# arduino_schDoc.net
KiCad netlist of a schematic drawn in Altium Designer
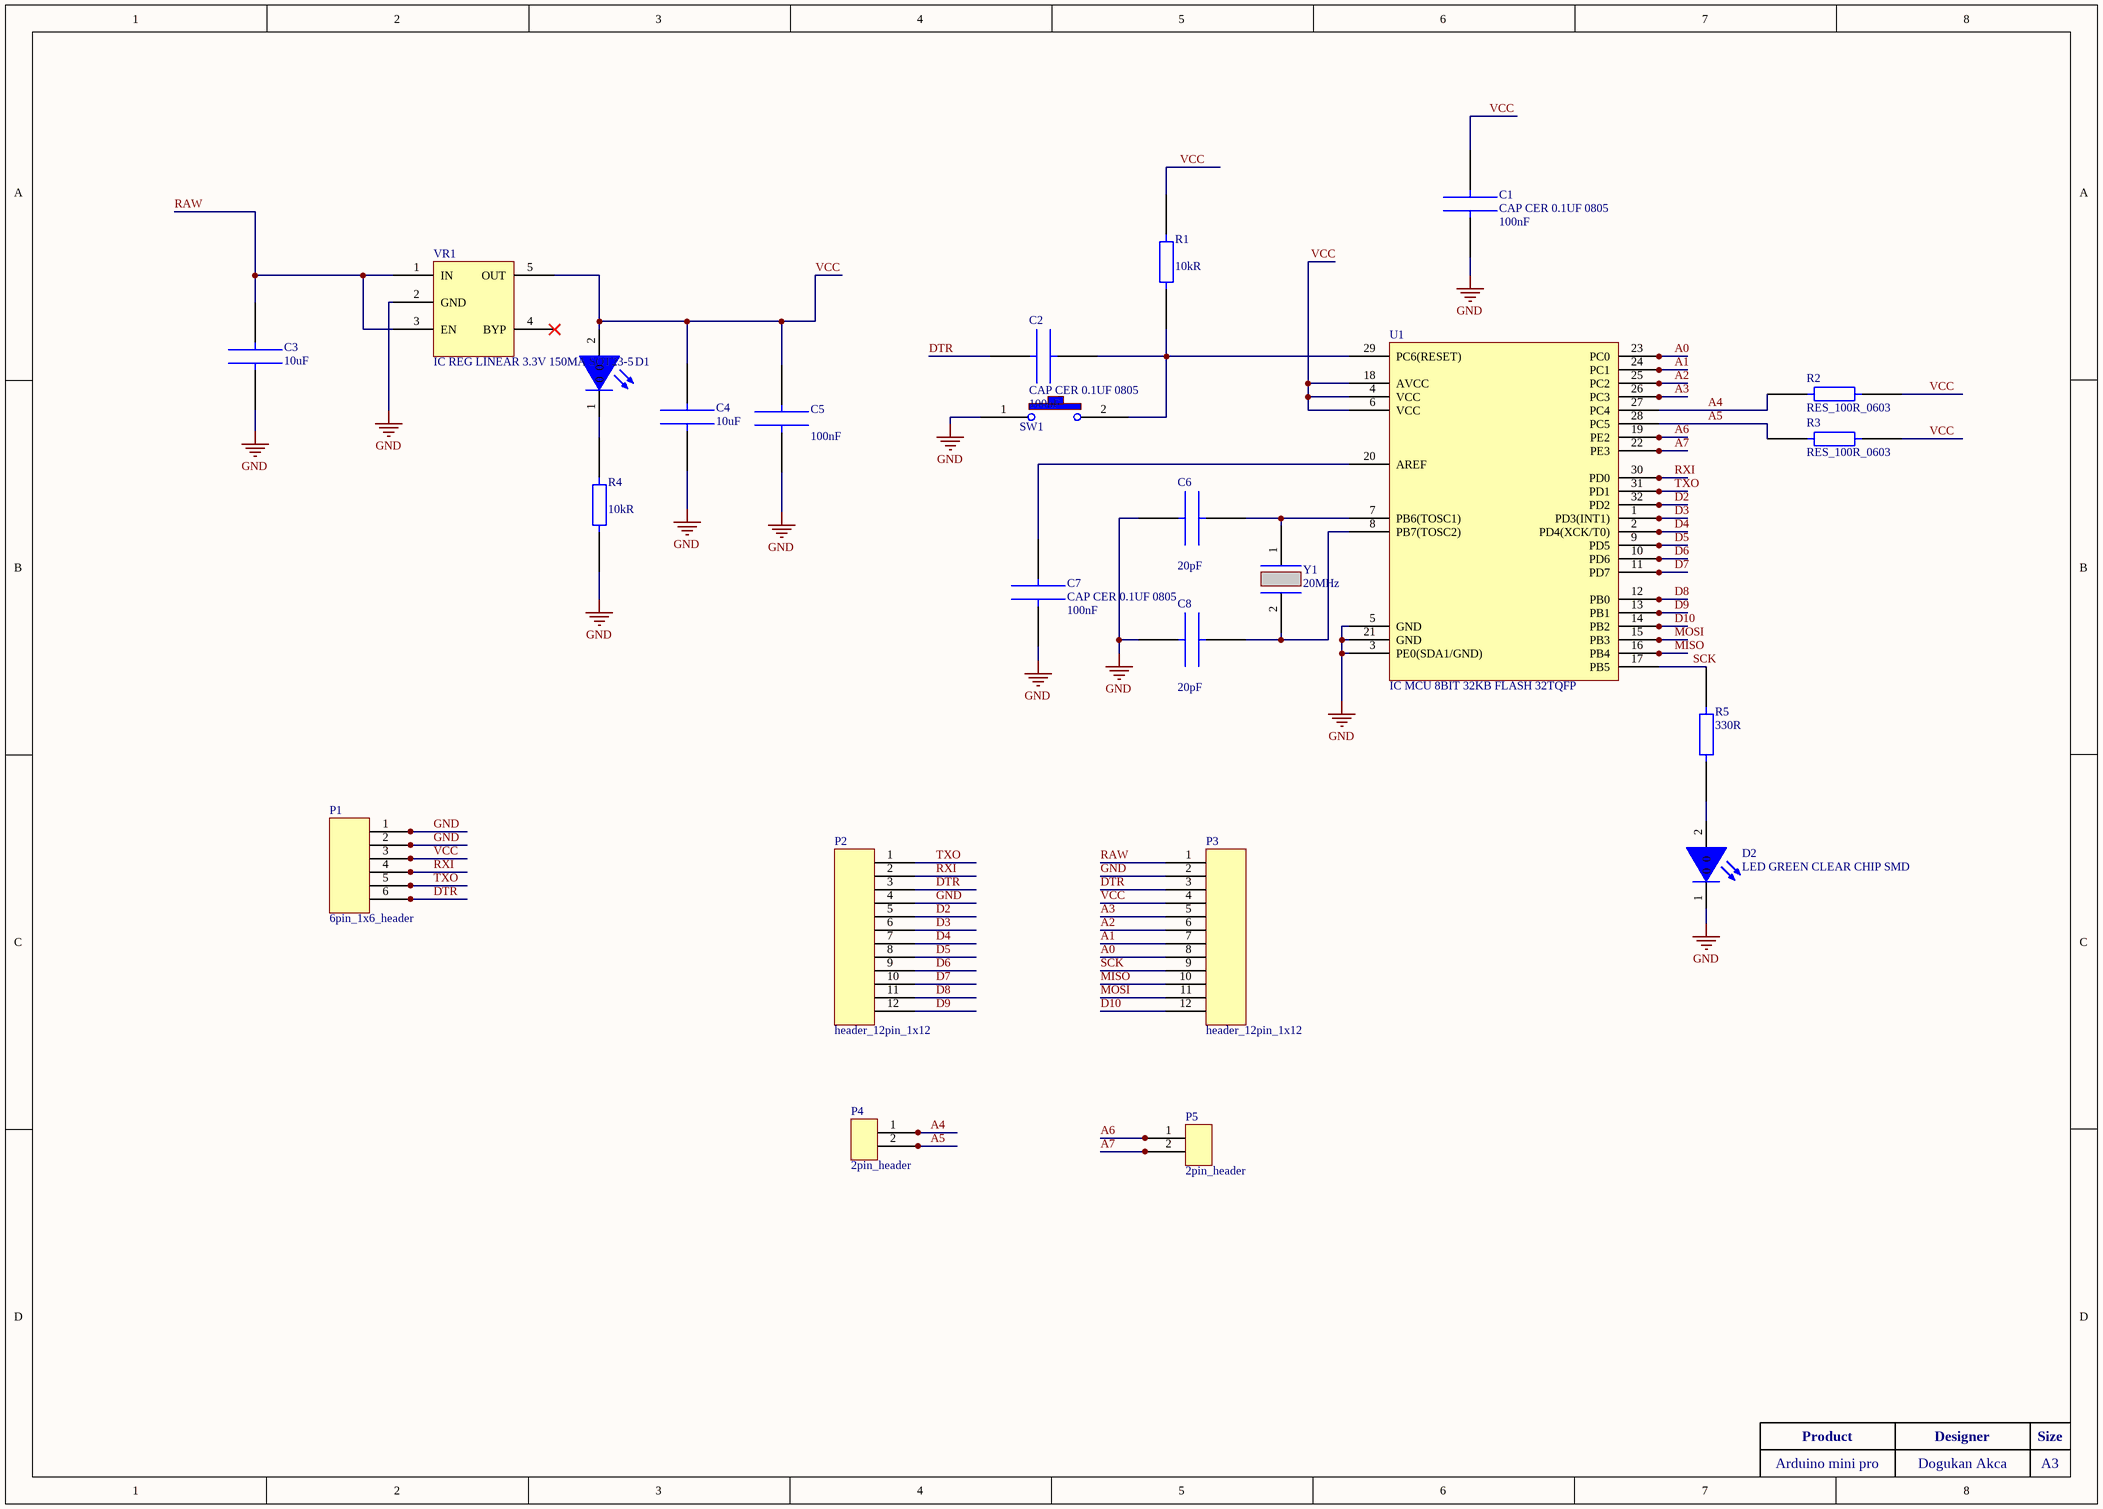
[diagram p0: arduino_schDoc.SchDoc]

(export (version "E")
  (design (tool "Eeschema 10.0.6"))
  (components
    (comp (ref "C1")
      (value "CAP CER 0.1UF 0805")
      (footprint "CAP_0805")
      (description "CAP CER 0.1UF 50V X7R 0805")
      (fields
        (field (name "MANUFACTURER") "Samsung")
        (field (name "MANUFACTURER PART NUMBER") "CL21B104KBCNNNC")
        (field (name "CAPACITANCE") "100nF")
        (field (name "DESIGNER") "Dogukan")
      )
      (libsource (lib "arduino_integratedLib") (part "CAP CER 0.1UF 0805"))
    )
    (comp (ref "C2")
      (value "CAP CER 0.1UF 0805")
      (footprint "CAP_0805")
      (description "CAP CER 0.1UF 50V X7R 0805")
      (fields
        (field (name "MANUFACTURER") "Samsung")
        (field (name "MANUFACTURER PART NUMBER") "CL21B104KBCNNNC")
        (field (name "CAPACITANCE") "100nF")
        (field (name "DESIGNER") "Dogukan")
      )
      (libsource (lib "arduino_integratedLib") (part "CAP CER 0.1UF 0805"))
    )
    (comp (ref "C3")
      (value "*CAP CER 10UF 4V X5R 0603")
      (footprint "0603_CAP")
      (description "0603 10 uF 4 V ±20% Tolerance X5R Multilayer Ceramic Capacitor")
      (fields
        (field (name "MANUFACTURER") "Yageo")
        (field (name "MANUFACTURER PART NUMBER") "CC0603MRX5R4BB106")
        (field (name "FARAD") "10uF")
        (field (name "DESIGNER") "Dogukan")
      )
      (libsource (lib "arduino_integratedLib") (part "CAP CER 10UF 4V X5R 0603"))
    )
    (comp (ref "C4")
      (value "*CAP CER 10UF 4V X5R 0603")
      (footprint "0603_CAP")
      (description "0603 10 uF 4 V ±20% Tolerance X5R Multilayer Ceramic Capacitor")
      (fields
        (field (name "MANUFACTURER") "Yageo")
        (field (name "MANUFACTURER PART NUMBER") "CC0603MRX5R4BB106")
        (field (name "FARAD") "10uF")
        (field (name "DESIGNER") "Dogukan")
      )
      (libsource (lib "arduino_integratedLib") (part "CAP CER 10UF 4V X5R 0603"))
    )
    (comp (ref "C5")
      (value "CAP CER 0.1UF 0805")
      (footprint "CAP_0805")
      (description "CAP CER 0.1UF 50V X7R 0805")
      (fields
        (field (name "MANUFACTURER") "Samsung")
        (field (name "MANUFACTURER PART NUMBER") "CL21B104KBCNNNC")
        (field (name "CAPACITANCE") "100nF")
        (field (name "DESIGNER") "Dogukan")
      )
      (libsource (lib "arduino_integratedLib") (part "CAP CER 0.1UF 0805"))
    )
    (comp (ref "C6")
      (value "CAP CER 20PF 50V C0G/NP0 0603")
      (footprint "0603_CAP")
      (fields
        (field (name "MANUFACTURER") "Samsung")
        (field (name "MANUFACTURER PART NUMBER") "CL10C200JB8NNNC")
        (field (name "TOLERANCE") "5%")
        (field (name "CAPACITANCE") "20pF")
        (field (name "DESIGNER") "Dogukan")
      )
      (libsource (lib "arduino_integratedLib") (part "CAP CER 20PF 50V C0G/NP0 0603"))
    )
    (comp (ref "C7")
      (value "CAP CER 0.1UF 0805")
      (footprint "CAP_0805")
      (description "CAP CER 0.1UF 50V X7R 0805")
      (fields
        (field (name "MANUFACTURER") "Samsung")
        (field (name "MANUFACTURER PART NUMBER") "CL21B104KBCNNNC")
        (field (name "CAPACITANCE") "100nF")
        (field (name "DESIGNER") "Dogukan")
      )
      (libsource (lib "arduino_integratedLib") (part "CAP CER 0.1UF 0805"))
    )
    (comp (ref "C8")
      (value "CAP CER 20PF 50V C0G/NP0 0603")
      (footprint "0603_CAP")
      (fields
        (field (name "MANUFACTURER") "Samsung")
        (field (name "MANUFACTURER PART NUMBER") "CL10C200JB8NNNC")
        (field (name "TOLERANCE") "5%")
        (field (name "CAPACITANCE") "20pF")
        (field (name "DESIGNER") "Dogukan")
      )
      (libsource (lib "arduino_integratedLib") (part "CAP CER 20PF 50V C0G/NP0 0603"))
    )
    (comp (ref "D1")
      (value "LED RED DIFFUSED 0805 SMD")
      (footprint "0805_RED_LED")
      (description "Red 645nm LED Indication - Discrete 1.8V 0805 (2012 Metric)")
      (fields (field (name "DESIGNER") "Dogukan"))
      (libsource (lib "arduino_integratedLib") (part "LED RED DIFFUSED 0805 SMD"))
    )
    (comp (ref "D2")
      (value "LED GREEN CLEAR CHIP SMD")
      (footprint "0805_LED_GREEN")
      (description "Green 569nm LED Indication - Discrete 2.1V 0805 (2012 Metric)")
      (fields
        (field (name "MANUFACTURER") "Vishay Lite-On")
        (field (name "MANUFACTURER PART NUMBER") "LTST-C171GKT")
        (field (name "DESIGNER") "Dogukan")
      )
      (libsource (lib "arduino_integratedLib") (part "LED GREEN CLEAR CHIP SMD"))
    )
    (comp (ref "P1")
      (value "6pin_1x6_header")
      (footprint "6_pin_header_1x6")
      (fields (field (name "DESIGNER") "Dogukan"))
      (libsource (lib "arduino_integratedLib") (part "6pin_1x6_header"))
    )
    (comp (ref "P2")
      (value "header_12pin_1x12")
      (footprint "12_pin_header_1x12")
      (fields (field (name "DESIGNER") "Dogukan"))
      (libsource (lib "arduino_integratedLib") (part "header_12pin_1x12"))
    )
    (comp (ref "P3")
      (value "header_12pin_1x12")
      (footprint "12_pin_header_1x12")
      (fields (field (name "DESIGNER") "Dogukan"))
      (libsource (lib "") (part "header_12pin_1x12_1"))
    )
    (comp (ref "P4")
      (value "2pin_header")
      (footprint "2pin_header_1x2")
      (fields (field (name "DESIGNER") "Dogukan"))
      (libsource (lib "") (part "2pin_header_1"))
    )
    (comp (ref "P5")
      (value "2pin_header")
      (footprint "2pin_header_1x2")
      (fields (field (name "DESIGNER") "Dogukan"))
      (libsource (lib "arduino_integratedLib") (part "2pin_header"))
    )
    (comp (ref "R1")
      (value "RES 10K OHM 0.5% 1/10W 0603")
      (footprint "0603_RES")
      (description "Res Thin Film 0603 10K Ohm 0.5% 1/10W ±25ppm/°C Molded SMD Paper T/R")
      (fields
        (field (name "MANUFACTURER") "Yageo")
        (field (name "MANUFACTURER PART NUMBER") "RT0603DRD0710KL")
        (field (name "RESISTANCE") "10kR")
        (field (name "DESIGNER") "Dogukan")
      )
      (libsource (lib "arduino_integratedLib") (part "RES 10K OHM 0.5% 1/10W 0603"))
    )
    (comp (ref "R2")
      (value "RES_100R_0603")
      (footprint "0603_RES")
      (description "Res Thick Film 0603 100 Ohm 1% 1/10W ±100ppm/°C Molded SMD Paper T/R")
      (fields
        (field (name "MANUFACTURER") "Yageo")
        (field (name "MANUFACTURER PART NUMBER") "RC0603FR-07100RL")
        (field (name "DESIGNER") "Dogukan")
      )
      (libsource (lib "arduino_integratedLib") (part "RES_100R_0603"))
    )
    (comp (ref "R3")
      (value "RES_100R_0603")
      (footprint "0603_RES")
      (description "Res Thick Film 0603 100 Ohm 1% 1/10W ±100ppm/°C Molded SMD Paper T/R")
      (fields
        (field (name "MANUFACTURER") "Yageo")
        (field (name "MANUFACTURER PART NUMBER") "RC0603FR-07100RL")
        (field (name "DESIGNER") "Dogukan")
      )
      (libsource (lib "arduino_integratedLib") (part "RES_100R_0603"))
    )
    (comp (ref "R4")
      (value "RES 10K OHM 0.5% 1/10W 0603")
      (footprint "0603_RES")
      (description "Res Thin Film 0603 10K Ohm 0.5% 1/10W ±25ppm/°C Molded SMD Paper T/R")
      (fields
        (field (name "MANUFACTURER") "Yageo")
        (field (name "MANUFACTURER PART NUMBER") "RT0603DRD0710KL")
        (field (name "RESISTANCE") "10kR")
        (field (name "DESIGNER") "Dogukan")
      )
      (libsource (lib "arduino_integratedLib") (part "RES 10K OHM 0.5% 1/10W 0603"))
    )
    (comp (ref "R5")
      (value "330R")
      (footprint "0603_RES")
      (description "Res Thick Film 0201 330 Ohm 1% 1/20W ±200ppm/°C Molded SMD SMD Paper T/R")
      (fields
        (field (name "MANUFACTURER") "Yageo")
        (field (name "MANUFACTURER PART NUMBER") "RC0201FR-07330RL")
        (field (name "DESIGNER") "Dogukan")
      )
      (libsource (lib "arduino_integratedLib") (part "RES 330 OHM 1% 1/20W 0201"))
    )
    (comp (ref "SW1")
      (value "push button switch")
      (footprint "push_button")
      (libsource (lib "arduino_integratedLib") (part "push_button"))
    )
    (comp (ref "U1")
      (value "IC MCU 8BIT 32KB FLASH 32TQFP")
      (footprint "32-TQFP")
      (description "AVR 32KBYTES Flash, 1KBYTES EEPROM, 2KBYTES Ram, W - 20MHZ, TQFP, Extended Temp, Green 5 V T&r")
      (fields
        (field (name "MANUFACTURER") "Microchip")
        (field (name "MANUFACTURER PART NUMBER") "ATMEGA328PB-ANR")
        (field (name "DESIGNER") "Dogukan")
      )
      (libsource (lib "arduino_integratedLib") (part "Atmega MCU 8BIT 32KB FLASH 32TQFP"))
    )
    (comp (ref "VR1")
      (value "IC REG LINEAR 3.3V 150MA SOT23-5")
      (footprint "SOT23-5")
      (description "Linear Voltage Regulator IC Positive Fixed 1 Output 3.3V 150mA SOT-23-5")
      (fields
        (field (name "MANUFACTURER") "Microchip")
        (field (name "MANUFACTURER PART NUMBER") "MIC5205-3.3YM5-TR")
        (field (name "DESIGNER") "Dogukan")
      )
      (libsource (lib "arduino_integratedLib") (part "IC REG LINEAR 3.3V 150MA SOT23-5"))
    )
    (comp (ref "Y1")
      (value "CRYSTAL 20.0000MHZ 20PF SMD")
      (footprint "2-SMD_CRYSTAL 32.7680KHZ")
      (description "Crystal 20MHz ±30ppm (Tol) ±50ppm (Stability) 20pF FUND 30Ohm 2-Pin Mini-SMD T/R")
      (fields
        (field (name "MANUFACTURER") "ECS International")
        (field (name "MANUFACTURER PART NUMBER") "ECS-200-20-23A-EN-TR")
        (field (name "FREQUENCY") "20MHz")
        (field (name "DESIGNER") "Dogukan")
      )
      (libsource (lib "arduino_integratedLib") (part "CRYSTAL 20MHZ SMD"))
    )
  )
  (nets
    (net (code "1") (name "/A0") (class "Default")
      (node (ref "P3") (pin "8") (pinfunction "8_8") (pintype "passive"))
      (node (ref "U1") (pin "23") (pinfunction "PC0_23") (pintype "passive"))
    )
    (net (code "2") (name "/A1") (class "Default")
      (node (ref "P3") (pin "7") (pinfunction "7_7") (pintype "passive"))
      (node (ref "U1") (pin "24") (pinfunction "PC1_24") (pintype "passive"))
    )
    (net (code "3") (name "/A2") (class "Default")
      (node (ref "P3") (pin "6") (pinfunction "6_6") (pintype "passive"))
      (node (ref "U1") (pin "25") (pinfunction "PC2_25") (pintype "passive"))
    )
    (net (code "4") (name "/A3") (class "Default")
      (node (ref "P3") (pin "5") (pinfunction "5_5") (pintype "passive"))
      (node (ref "U1") (pin "26") (pinfunction "PC3_26") (pintype "passive"))
    )
    (net (code "5") (name "/A4") (class "Default")
      (node (ref "P4") (pin "1") (pinfunction "1_1") (pintype "passive"))
      (node (ref "R2") (pin "1") (pinfunction "25_1") (pintype "passive"))
      (node (ref "U1") (pin "27") (pinfunction "PC4_27") (pintype "passive"))
    )
    (net (code "6") (name "/A5") (class "Default")
      (node (ref "P4") (pin "2") (pinfunction "2_2") (pintype "passive"))
      (node (ref "R3") (pin "1") (pinfunction "25_1") (pintype "passive"))
      (node (ref "U1") (pin "28") (pinfunction "PC5_28") (pintype "passive"))
    )
    (net (code "7") (name "/A6") (class "Default")
      (node (ref "P5") (pin "1") (pinfunction "1_1") (pintype "passive"))
      (node (ref "U1") (pin "19") (pinfunction "PE2_19") (pintype "passive"))
    )
    (net (code "8") (name "/A7") (class "Default")
      (node (ref "P5") (pin "2") (pinfunction "2_2") (pintype "passive"))
      (node (ref "U1") (pin "22") (pinfunction "PE3_22") (pintype "passive"))
    )
    (net (code "9") (name "/D2") (class "Default")
      (node (ref "P2") (pin "5") (pinfunction "5_5") (pintype "passive"))
      (node (ref "U1") (pin "32") (pinfunction "PD2_32") (pintype "passive"))
    )
    (net (code "10") (name "/D3") (class "Default")
      (node (ref "P2") (pin "6") (pinfunction "6_6") (pintype "passive"))
      (node (ref "U1") (pin "1") (pinfunction "PD3(INT1)_1") (pintype "passive"))
    )
    (net (code "11") (name "/D4") (class "Default")
      (node (ref "P2") (pin "7") (pinfunction "7_7") (pintype "passive"))
      (node (ref "U1") (pin "2") (pinfunction "PD4(XCK/T0)_2") (pintype "passive"))
    )
    (net (code "12") (name "/D5") (class "Default")
      (node (ref "P2") (pin "8") (pinfunction "8_8") (pintype "passive"))
      (node (ref "U1") (pin "9") (pinfunction "PD5_9") (pintype "passive"))
    )
    (net (code "13") (name "/D6") (class "Default")
      (node (ref "P2") (pin "9") (pinfunction "9_9") (pintype "passive"))
      (node (ref "U1") (pin "10") (pinfunction "PD6_10") (pintype "passive"))
    )
    (net (code "14") (name "/D7") (class "Default")
      (node (ref "P2") (pin "10") (pinfunction "10_10") (pintype "passive"))
      (node (ref "U1") (pin "11") (pinfunction "PD7_11") (pintype "passive"))
    )
    (net (code "15") (name "/D8") (class "Default")
      (node (ref "P2") (pin "11") (pinfunction "11_11") (pintype "passive"))
      (node (ref "U1") (pin "12") (pinfunction "PB0_12") (pintype "passive"))
    )
    (net (code "16") (name "/D9") (class "Default")
      (node (ref "P2") (pin "12") (pinfunction "12_12") (pintype "passive"))
      (node (ref "U1") (pin "13") (pinfunction "PB1_13") (pintype "passive"))
    )
    (net (code "17") (name "/D10") (class "Default")
      (node (ref "P3") (pin "12") (pinfunction "12_12") (pintype "passive"))
      (node (ref "U1") (pin "14") (pinfunction "PB2_14") (pintype "passive"))
    )
    (net (code "18") (name "/DTR") (class "Default")
      (node (ref "C2") (pin "1") (pinfunction "26_1") (pintype "passive"))
      (node (ref "P1") (pin "6") (pinfunction "6_6") (pintype "passive"))
      (node (ref "P2") (pin "3") (pinfunction "3_3") (pintype "passive"))
      (node (ref "P3") (pin "3") (pinfunction "3_3") (pintype "passive"))
    )
    (net (code "19") (name "/MISO") (class "Default")
      (node (ref "P3") (pin "10") (pinfunction "10_10") (pintype "passive"))
      (node (ref "U1") (pin "16") (pinfunction "PB4_16") (pintype "passive"))
    )
    (net (code "20") (name "/MOSI") (class "Default")
      (node (ref "P3") (pin "11") (pinfunction "11_11") (pintype "passive"))
      (node (ref "U1") (pin "15") (pinfunction "PB3_15") (pintype "passive"))
    )
    (net (code "21") (name "/RAW") (class "Default")
      (node (ref "C3") (pin "2") (pinfunction "27_2") (pintype "passive"))
      (node (ref "P3") (pin "1") (pinfunction "1_1") (pintype "passive"))
      (node (ref "VR1") (pin "1") (pinfunction "IN_1") (pintype "passive"))
      (node (ref "VR1") (pin "3") (pinfunction "EN_3") (pintype "passive"))
    )
    (net (code "22") (name "/RXI") (class "Default")
      (node (ref "P1") (pin "4") (pinfunction "4_4") (pintype "passive"))
      (node (ref "P2") (pin "2") (pinfunction "2_2") (pintype "passive"))
      (node (ref "U1") (pin "30") (pinfunction "PD0_30") (pintype "passive"))
    )
    (net (code "23") (name "/SCK") (class "Default")
      (node (ref "P3") (pin "9") (pinfunction "9_9") (pintype "passive"))
      (node (ref "R5") (pin "2") (pinfunction "24_2") (pintype "passive"))
      (node (ref "U1") (pin "17") (pinfunction "PB5_17") (pintype "passive"))
    )
    (net (code "24") (name "/TXO") (class "Default")
      (node (ref "P1") (pin "5") (pinfunction "5_5") (pintype "passive"))
      (node (ref "P2") (pin "1") (pinfunction "1_1") (pintype "passive"))
      (node (ref "U1") (pin "31") (pinfunction "PD1_31") (pintype "passive"))
    )
    (net (code "25") (name "/VCC") (class "Default")
      (node (ref "C1") (pin "2") (pinfunction "27_2") (pintype "passive"))
      (node (ref "C4") (pin "2") (pinfunction "27_2") (pintype "passive"))
      (node (ref "C5") (pin "2") (pinfunction "27_2") (pintype "passive"))
      (node (ref "D1") (pin "2") (pinfunction "0_2") (pintype "passive"))
      (node (ref "P1") (pin "3") (pinfunction "3_3") (pintype "passive"))
      (node (ref "P3") (pin "4") (pinfunction "4_4") (pintype "passive"))
      (node (ref "R1") (pin "2") (pinfunction "24_2") (pintype "passive"))
      (node (ref "R2") (pin "2") (pinfunction "24_2") (pintype "passive"))
      (node (ref "R3") (pin "2") (pinfunction "24_2") (pintype "passive"))
      (node (ref "U1") (pin "18") (pinfunction "AVCC_18") (pintype "passive"))
      (node (ref "U1") (pin "4") (pinfunction "VCC_4") (pintype "passive"))
      (node (ref "U1") (pin "6") (pinfunction "VCC_6") (pintype "passive"))
      (node (ref "VR1") (pin "5") (pinfunction "OUT_5") (pintype "passive"))
    )
    (net (code "26") (name "GND") (class "Default")
      (node (ref "C1") (pin "1") (pinfunction "26_1") (pintype "passive"))
      (node (ref "C3") (pin "1") (pinfunction "26_1") (pintype "passive"))
      (node (ref "C4") (pin "1") (pinfunction "26_1") (pintype "passive"))
      (node (ref "C5") (pin "1") (pinfunction "26_1") (pintype "passive"))
      (node (ref "C6") (pin "1") (pinfunction "26_1") (pintype "passive"))
      (node (ref "C7") (pin "1") (pinfunction "26_1") (pintype "passive"))
      (node (ref "C8") (pin "1") (pinfunction "26_1") (pintype "passive"))
      (node (ref "D2") (pin "1") (pinfunction "0_1") (pintype "passive"))
      (node (ref "P1") (pin "1") (pinfunction "1_1") (pintype "passive"))
      (node (ref "P1") (pin "2") (pinfunction "2_2") (pintype "passive"))
      (node (ref "P2") (pin "4") (pinfunction "4_4") (pintype "passive"))
      (node (ref "P3") (pin "2") (pinfunction "2_2") (pintype "passive"))
      (node (ref "R4") (pin "1") (pinfunction "25_1") (pintype "passive"))
      (node (ref "SW1") (pin "1") (pinfunction "1_1") (pintype "passive"))
      (node (ref "U1") (pin "21") (pinfunction "GND_21") (pintype "passive"))
      (node (ref "U1") (pin "3") (pinfunction "PE0(SDA1/GND)_3") (pintype "passive"))
      (node (ref "U1") (pin "5") (pinfunction "GND_5") (pintype "passive"))
      (node (ref "VR1") (pin "2") (pinfunction "GND_2") (pintype "passive"))
    )
    (net (code "27") (name "Net-(C2-27)") (class "Default")
      (node (ref "C2") (pin "2") (pinfunction "27_2") (pintype "passive"))
      (node (ref "R1") (pin "1") (pinfunction "25_1") (pintype "passive"))
      (node (ref "SW1") (pin "2") (pinfunction "2_2") (pintype "passive"))
      (node (ref "U1") (pin "29") (pinfunction "PC6(RESET)_29") (pintype "passive"))
    )
    (net (code "28") (name "Net-(C6-27)") (class "Default")
      (node (ref "C6") (pin "2") (pinfunction "27_2") (pintype "passive"))
      (node (ref "U1") (pin "7") (pinfunction "PB6(TOSC1)_7") (pintype "passive"))
      (node (ref "Y1") (pin "1") (pinfunction "4_1") (pintype "passive"))
    )
    (net (code "29") (name "Net-(C7-27)") (class "Default")
      (node (ref "C7") (pin "2") (pinfunction "27_2") (pintype "passive"))
      (node (ref "U1") (pin "20") (pinfunction "AREF_20") (pintype "passive"))
    )
    (net (code "30") (name "Net-(C8-27)") (class "Default")
      (node (ref "C8") (pin "2") (pinfunction "27_2") (pintype "passive"))
      (node (ref "U1") (pin "8") (pinfunction "PB7(TOSC2)_8") (pintype "passive"))
      (node (ref "Y1") (pin "2") (pinfunction "5_2") (pintype "passive"))
    )
    (net (code "31") (name "Net-(R4-24)") (class "Default")
      (node (ref "D1") (pin "1") (pinfunction "0_1") (pintype "passive"))
      (node (ref "R4") (pin "2") (pinfunction "24_2") (pintype "passive"))
    )
    (net (code "32") (name "Net-(R5-25)") (class "Default")
      (node (ref "D2") (pin "2") (pinfunction "0_2") (pintype "passive"))
      (node (ref "R5") (pin "1") (pinfunction "25_1") (pintype "passive"))
    )
    (net (code "33") (name "unconnected-(VR1-BYP-Pad4)") (class "Default")
      (node (ref "VR1") (pin "4") (pinfunction "BYP_4") (pintype "passive+no_connect"))
    )
  )
)
